# SCH_Irrigador-Autom_tico-Trato_2026-02-0.net
KiCad netlist of a schematic drawn in EasyEDA
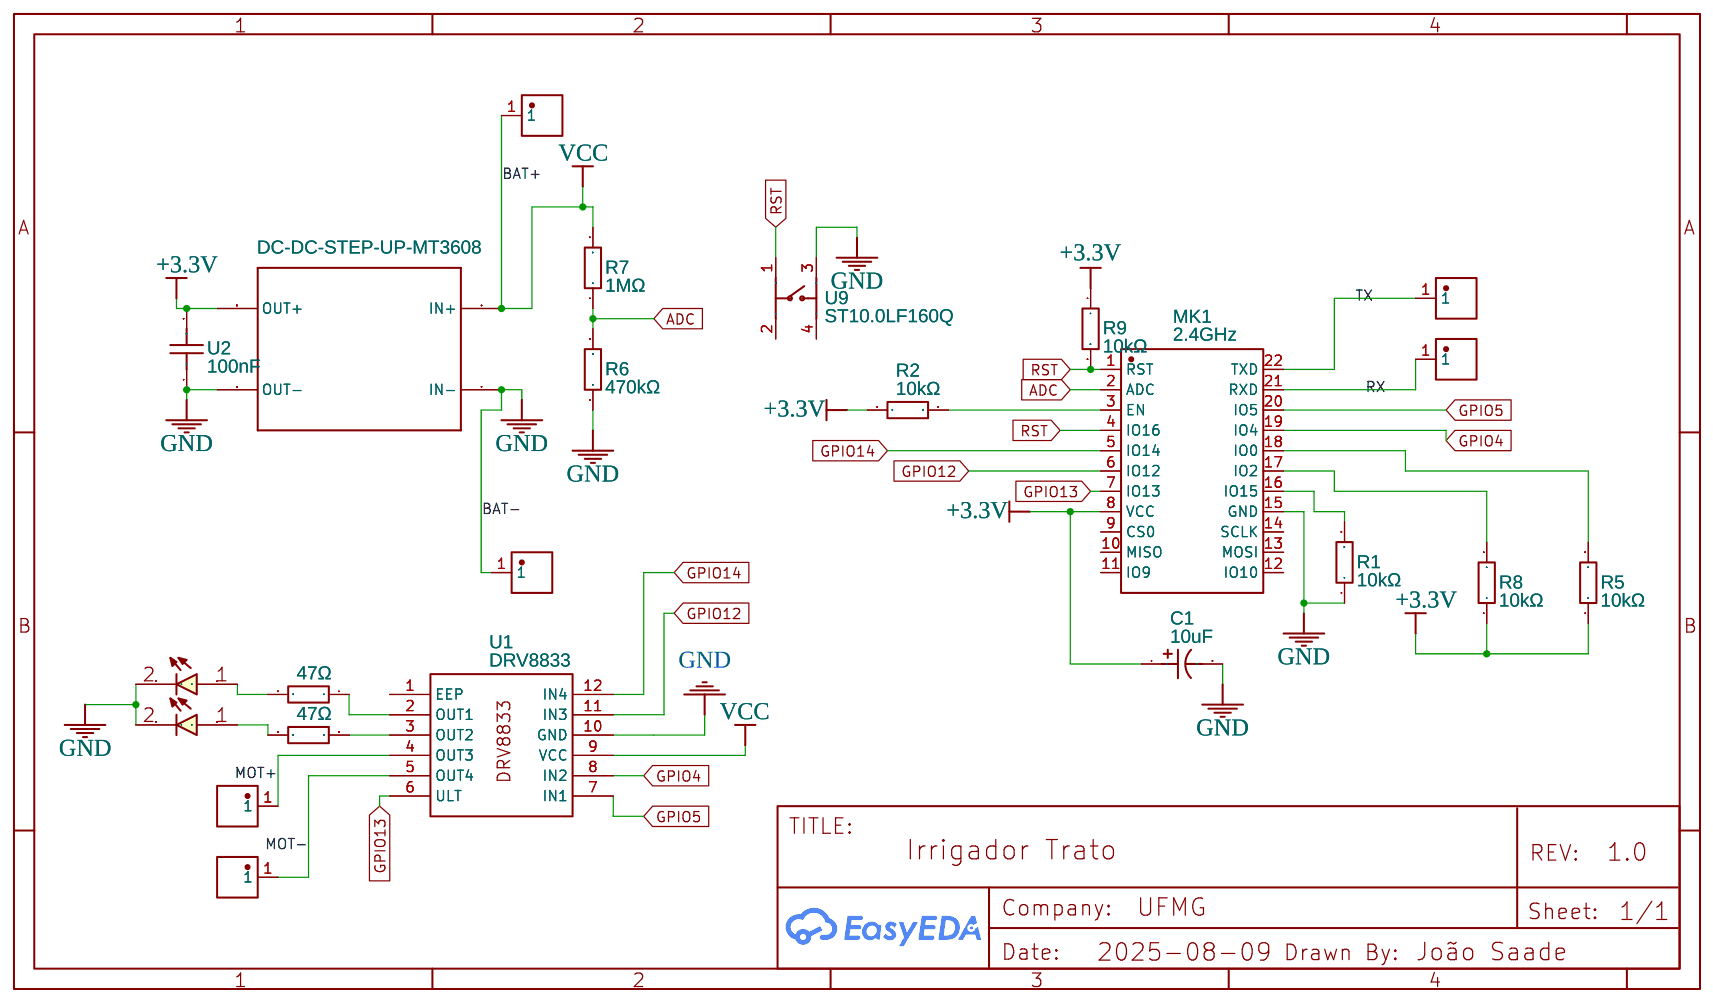
[diagram p0: schematic sheet]

(export (version "E")
  (design (tool "Eeschema 10.0.6"))
  (components
    (comp (ref "2") (value "DC-DC-STEP-UP-MT3608") (libsource (lib "") (part "DC-DC-STEP-UP-MT3608")))
    (comp (ref "C1")
      (value "10uF")
      (fields
        (field (name "Manufacturer Part") "NXA50V10M5*11 2.5TP")
        (field (name "Manufacturer") "SAMYOUNG(韩国三莹)")
      )
      (libsource (lib "") (part "NXA50V10M5*11 2.5TP"))
    )
    (comp (ref "LED3") (value "LED-5MM-RED") (libsource (lib "") (part "LED-5MM-RED")))
    (comp (ref "LED4") (value "LED-5MM-GRE") (libsource (lib "") (part "LED-5MM-GRE")))
    (comp (ref "MK1")
      (value "2.4GHz")
      (fields (field (name "Manufacturer Part") "ESP-12E") (field (name "Manufacturer") "Ai-Thinker(安信可)"))
      (libsource (lib "") (part "ESP-12E"))
    )
    (comp (ref "R1")
      (value "10kΩ")
      (fields
        (field (name "Manufacturer Part") "CF1/4W-110KΩ±5% T52")
        (field (name "Manufacturer") "CCO(千志电子)")
      )
      (libsource (lib "") (part "CF1/4W-110KΩ±5% T52_1"))
    )
    (comp (ref "R2")
      (value "10kΩ")
      (fields
        (field (name "Manufacturer Part") "CF1/4W-110KΩ±5% T52")
        (field (name "Manufacturer") "CCO(千志电子)")
      )
      (libsource (lib "") (part "CF1/4W-110KΩ±5% T52"))
    )
    (comp (ref "R3")
      (value "47Ω")
      (fields
        (field (name "Manufacturer Part") "CF1/4W-110KΩ±5% T52")
        (field (name "Manufacturer") "CCO(千志电子)")
      )
      (libsource (lib "") (part "CF1/4W-110KΩ±5% T52"))
    )
    (comp (ref "R4")
      (value "47Ω")
      (fields
        (field (name "Manufacturer Part") "CF1/4W-110KΩ±5% T52")
        (field (name "Manufacturer") "CCO(千志电子)")
      )
      (libsource (lib "") (part "CF1/4W-110KΩ±5% T52"))
    )
    (comp (ref "R5")
      (value "10kΩ")
      (fields
        (field (name "Manufacturer Part") "CF1/4W-110KΩ±5% T52")
        (field (name "Manufacturer") "CCO(千志电子)")
      )
      (libsource (lib "") (part "CF1/4W-110KΩ±5% T52_1"))
    )
    (comp (ref "R6")
      (value "470kΩ")
      (fields
        (field (name "Manufacturer Part") "CF1/4W-110KΩ±5% T52")
        (field (name "Manufacturer") "CCO(千志电子)")
      )
      (libsource (lib "") (part "CF1/4W-110KΩ±5% T52_1"))
    )
    (comp (ref "R7")
      (value "1MΩ")
      (fields
        (field (name "Manufacturer Part") "CF1/4W-110KΩ±5% T52")
        (field (name "Manufacturer") "CCO(千志电子)")
      )
      (libsource (lib "") (part "CF1/4W-110KΩ±5% T52_1"))
    )
    (comp (ref "R8")
      (value "10kΩ")
      (fields
        (field (name "Manufacturer Part") "CF1/4W-110KΩ±5% T52")
        (field (name "Manufacturer") "CCO(千志电子)")
      )
      (libsource (lib "") (part "CF1/4W-110KΩ±5% T52_1"))
    )
    (comp (ref "R9")
      (value "10kΩ")
      (fields
        (field (name "Manufacturer Part") "CF1/4W-110KΩ±5% T52")
        (field (name "Manufacturer") "CCO(千志电子)")
      )
      (libsource (lib "") (part "CF1/4W-110KΩ±5% T52_2"))
    )
    (comp (ref "U1")
      (value "DRV8833")
      (fields (field (name "Manufacturer") "TI"))
      (libsource (lib "") (part "DRV8833"))
    )
    (comp (ref "U2")
      (value "100nF")
      (fields (field (name "Manufacturer Part") "K104K10X7RF5UH5") (field (name "Manufacturer") "VISHAY(威世)"))
      (libsource (lib "") (part "K104K10X7RF5UH5"))
    )
    (comp (ref "U9")
      (value "ST10.0LF160Q")
      (fields (field (name "Manufacturer") "CIT Relay and Switch"))
      (libsource (lib "") (part "ST10.0LF160Q"))
    )
    (comp (ref "U11")
      (value "P70-2200045")
      (fields (field (name "Manufacturer") "Harwin"))
      (libsource (lib "") (part "P70-2200045"))
    )
    (comp (ref "U12")
      (value "P70-2200045")
      (fields (field (name "Manufacturer") "Harwin"))
      (libsource (lib "") (part "P70-2200045"))
    )
    (comp (ref "U13")
      (value "P70-2200045")
      (fields (field (name "Manufacturer") "Harwin"))
      (libsource (lib "") (part "P70-2200045_1"))
    )
    (comp (ref "U14")
      (value "P70-2200045")
      (fields (field (name "Manufacturer") "Harwin"))
      (libsource (lib "") (part "P70-2200045_1"))
    )
    (comp (ref "U15")
      (value "P70-2200045")
      (fields (field (name "Manufacturer") "Harwin"))
      (libsource (lib "") (part "P70-2200045_1"))
    )
    (comp (ref "U16")
      (value "P70-2200045")
      (fields (field (name "Manufacturer") "Harwin"))
      (libsource (lib "") (part "P70-2200045_1"))
    )
  )
  (nets
    (net (code "1") (name "+3.3V") (class "Default")
      (node (ref "2") (pin "OUT+") (pinfunction "OUT+_OUT+") (pintype "bidirectional"))
      (node (ref "C1") (pin "1") (pinfunction "1_1") (pintype "input"))
      (node (ref "MK1") (pin "8") (pinfunction "VCC_8") (pintype "unspecified"))
      (node (ref "R2") (pin "2") (pinfunction "2_2") (pintype "unspecified"))
      (node (ref "R5") (pin "1") (pinfunction "1_1") (pintype "unspecified"))
      (node (ref "R8") (pin "1") (pinfunction "1_1") (pintype "unspecified"))
      (node (ref "R9") (pin "1") (pinfunction "1_1") (pintype "unspecified"))
      (node (ref "U2") (pin "2") (pinfunction "2_2") (pintype "unspecified"))
    )
    (net (code "2") (name "/MOT+") (class "Default")
      (node (ref "U1") (pin "4") (pinfunction "OUT3_4") (pintype "unspecified"))
      (node (ref "U12") (pin "1") (pinfunction "1_1") (pintype "unspecified"))
    )
    (net (code "3") (name "/MOT-") (class "Default")
      (node (ref "U1") (pin "5") (pinfunction "OUT4_5") (pintype "unspecified"))
      (node (ref "U11") (pin "1") (pinfunction "1_1") (pintype "unspecified"))
    )
    (net (code "4") (name "/RX") (class "Default")
      (node (ref "MK1") (pin "21") (pinfunction "RXD_21") (pintype "unspecified"))
      (node (ref "U13") (pin "1") (pinfunction "1_1") (pintype "unspecified"))
    )
    (net (code "5") (name "/TX") (class "Default")
      (node (ref "MK1") (pin "22") (pinfunction "TXD_22") (pintype "unspecified"))
      (node (ref "U14") (pin "1") (pinfunction "1_1") (pintype "unspecified"))
    )
    (net (code "6") (name "ADC") (class "Default")
      (node (ref "MK1") (pin "2") (pinfunction "ADC_2") (pintype "unspecified"))
      (node (ref "R6") (pin "2") (pinfunction "2_2") (pintype "unspecified"))
      (node (ref "R7") (pin "1") (pinfunction "1_1") (pintype "unspecified"))
    )
    (net (code "7") (name "GND") (class "Default")
      (node (ref "2") (pin "IN-") (pinfunction "IN-_IN-") (pintype "bidirectional"))
      (node (ref "2") (pin "OUT-") (pinfunction "OUT-_OUT-") (pintype "bidirectional"))
      (node (ref "C1") (pin "2") (pinfunction "2_2") (pintype "input"))
      (node (ref "LED3") (pin "2") (pinfunction "K_2") (pintype "unspecified"))
      (node (ref "LED4") (pin "2") (pinfunction "K_2") (pintype "unspecified"))
      (node (ref "MK1") (pin "15") (pinfunction "GND_15") (pintype "unspecified"))
      (node (ref "R1") (pin "1") (pinfunction "1_1") (pintype "unspecified"))
      (node (ref "R6") (pin "1") (pinfunction "1_1") (pintype "unspecified"))
      (node (ref "U1") (pin "10") (pinfunction "GND_10") (pintype "unspecified"))
      (node (ref "U16") (pin "1") (pinfunction "1_1") (pintype "unspecified"))
      (node (ref "U2") (pin "1") (pinfunction "1_1") (pintype "unspecified"))
      (node (ref "U9") (pin "3") (pinfunction "3_3") (pintype "unspecified"))
    )
    (net (code "8") (name "GPIO4") (class "Default")
      (node (ref "MK1") (pin "19") (pinfunction "IO4_19") (pintype "unspecified"))
      (node (ref "U1") (pin "8") (pinfunction "IN2_8") (pintype "unspecified"))
    )
    (net (code "9") (name "GPIO5") (class "Default")
      (node (ref "MK1") (pin "20") (pinfunction "IO5_20") (pintype "unspecified"))
      (node (ref "U1") (pin "7") (pinfunction "IN1_7") (pintype "unspecified"))
    )
    (net (code "10") (name "GPIO12") (class "Default")
      (node (ref "MK1") (pin "6") (pinfunction "IO12_6") (pintype "unspecified"))
      (node (ref "U1") (pin "11") (pinfunction "IN3_11") (pintype "unspecified"))
    )
    (net (code "11") (name "GPIO13") (class "Default")
      (node (ref "MK1") (pin "7") (pinfunction "IO13_7") (pintype "unspecified"))
      (node (ref "U1") (pin "6") (pinfunction "ULT_6") (pintype "unspecified"))
    )
    (net (code "12") (name "GPIO14") (class "Default")
      (node (ref "MK1") (pin "5") (pinfunction "IO14_5") (pintype "unspecified"))
      (node (ref "U1") (pin "12") (pinfunction "IN4_12") (pintype "unspecified"))
    )
    (net (code "13") (name "Net-(LED3-A)") (class "Default")
      (node (ref "LED3") (pin "1") (pinfunction "A_1") (pintype "unspecified"))
      (node (ref "R4") (pin "2") (pinfunction "2_2") (pintype "unspecified"))
    )
    (net (code "14") (name "Net-(LED4-A)") (class "Default")
      (node (ref "LED4") (pin "1") (pinfunction "A_1") (pintype "unspecified"))
      (node (ref "R3") (pin "2") (pinfunction "2_2") (pintype "unspecified"))
    )
    (net (code "15") (name "Net-(MK1-EN)") (class "Default")
      (node (ref "MK1") (pin "3") (pinfunction "EN_3") (pintype "unspecified"))
      (node (ref "R2") (pin "1") (pinfunction "1_1") (pintype "unspecified"))
    )
    (net (code "16") (name "Net-(MK1-IO0)") (class "Default")
      (node (ref "MK1") (pin "18") (pinfunction "IO0_18") (pintype "unspecified"))
      (node (ref "R5") (pin "2") (pinfunction "2_2") (pintype "unspecified"))
    )
    (net (code "17") (name "Net-(MK1-IO2)") (class "Default")
      (node (ref "MK1") (pin "17") (pinfunction "IO2_17") (pintype "unspecified"))
      (node (ref "R8") (pin "2") (pinfunction "2_2") (pintype "unspecified"))
    )
    (net (code "18") (name "Net-(MK1-IO15)") (class "Default")
      (node (ref "MK1") (pin "16") (pinfunction "IO15_16") (pintype "unspecified"))
      (node (ref "R1") (pin "2") (pinfunction "2_2") (pintype "unspecified"))
    )
    (net (code "19") (name "Net-(U1-OUT1)") (class "Default")
      (node (ref "R3") (pin "1") (pinfunction "1_1") (pintype "unspecified"))
      (node (ref "U1") (pin "2") (pinfunction "OUT1_2") (pintype "unspecified"))
    )
    (net (code "20") (name "Net-(U1-OUT2)") (class "Default")
      (node (ref "R4") (pin "1") (pinfunction "1_1") (pintype "unspecified"))
      (node (ref "U1") (pin "3") (pinfunction "OUT2_3") (pintype "unspecified"))
    )
    (net (code "21") (name "RST") (class "Default")
      (node (ref "MK1") (pin "1") (pinfunction "RST_1") (pintype "unspecified"))
      (node (ref "MK1") (pin "4") (pinfunction "IO16_4") (pintype "unspecified"))
      (node (ref "R9") (pin "2") (pinfunction "2_2") (pintype "unspecified"))
      (node (ref "U9") (pin "1") (pinfunction "1_1") (pintype "unspecified"))
    )
    (net (code "22") (name "VCC") (class "Default")
      (node (ref "2") (pin "IN+") (pinfunction "IN+_IN+") (pintype "bidirectional"))
      (node (ref "R7") (pin "2") (pinfunction "2_2") (pintype "unspecified"))
      (node (ref "U1") (pin "9") (pinfunction "VCC_9") (pintype "unspecified"))
      (node (ref "U15") (pin "1") (pinfunction "1_1") (pintype "unspecified"))
    )
    (net (code "23") (name "unconnected-(MK1-CS0-Pad9)") (class "Default")
      (node (ref "MK1") (pin "9") (pinfunction "CS0_9") (pintype "unspecified"))
    )
    (net (code "24") (name "unconnected-(MK1-IO9-Pad11)") (class "Default")
      (node (ref "MK1") (pin "11") (pinfunction "IO9_11") (pintype "unspecified"))
    )
    (net (code "25") (name "unconnected-(MK1-IO10-Pad12)") (class "Default")
      (node (ref "MK1") (pin "12") (pinfunction "IO10_12") (pintype "unspecified"))
    )
    (net (code "26") (name "unconnected-(MK1-MISO-Pad10)") (class "Default")
      (node (ref "MK1") (pin "10") (pinfunction "MISO_10") (pintype "unspecified"))
    )
    (net (code "27") (name "unconnected-(MK1-MOSI-Pad13)") (class "Default")
      (node (ref "MK1") (pin "13") (pinfunction "MOSI_13") (pintype "unspecified"))
    )
    (net (code "28") (name "unconnected-(MK1-SCLK-Pad14)") (class "Default")
      (node (ref "MK1") (pin "14") (pinfunction "SCLK_14") (pintype "unspecified"))
    )
    (net (code "29") (name "unconnected-(U1-EEP-Pad1)") (class "Default")
      (node (ref "U1") (pin "1") (pinfunction "EEP_1") (pintype "unspecified"))
    )
    (net (code "30") (name "unconnected-(U9-Pad2)") (class "Default")
      (node (ref "U9") (pin "2") (pinfunction "2_2") (pintype "unspecified"))
    )
    (net (code "31") (name "unconnected-(U9-Pad4)") (class "Default")
      (node (ref "U9") (pin "4") (pinfunction "4_4") (pintype "unspecified"))
    )
  )
)
